# vd_using_sym.net
KiCad netlist of a schematic drawn in EAGLE
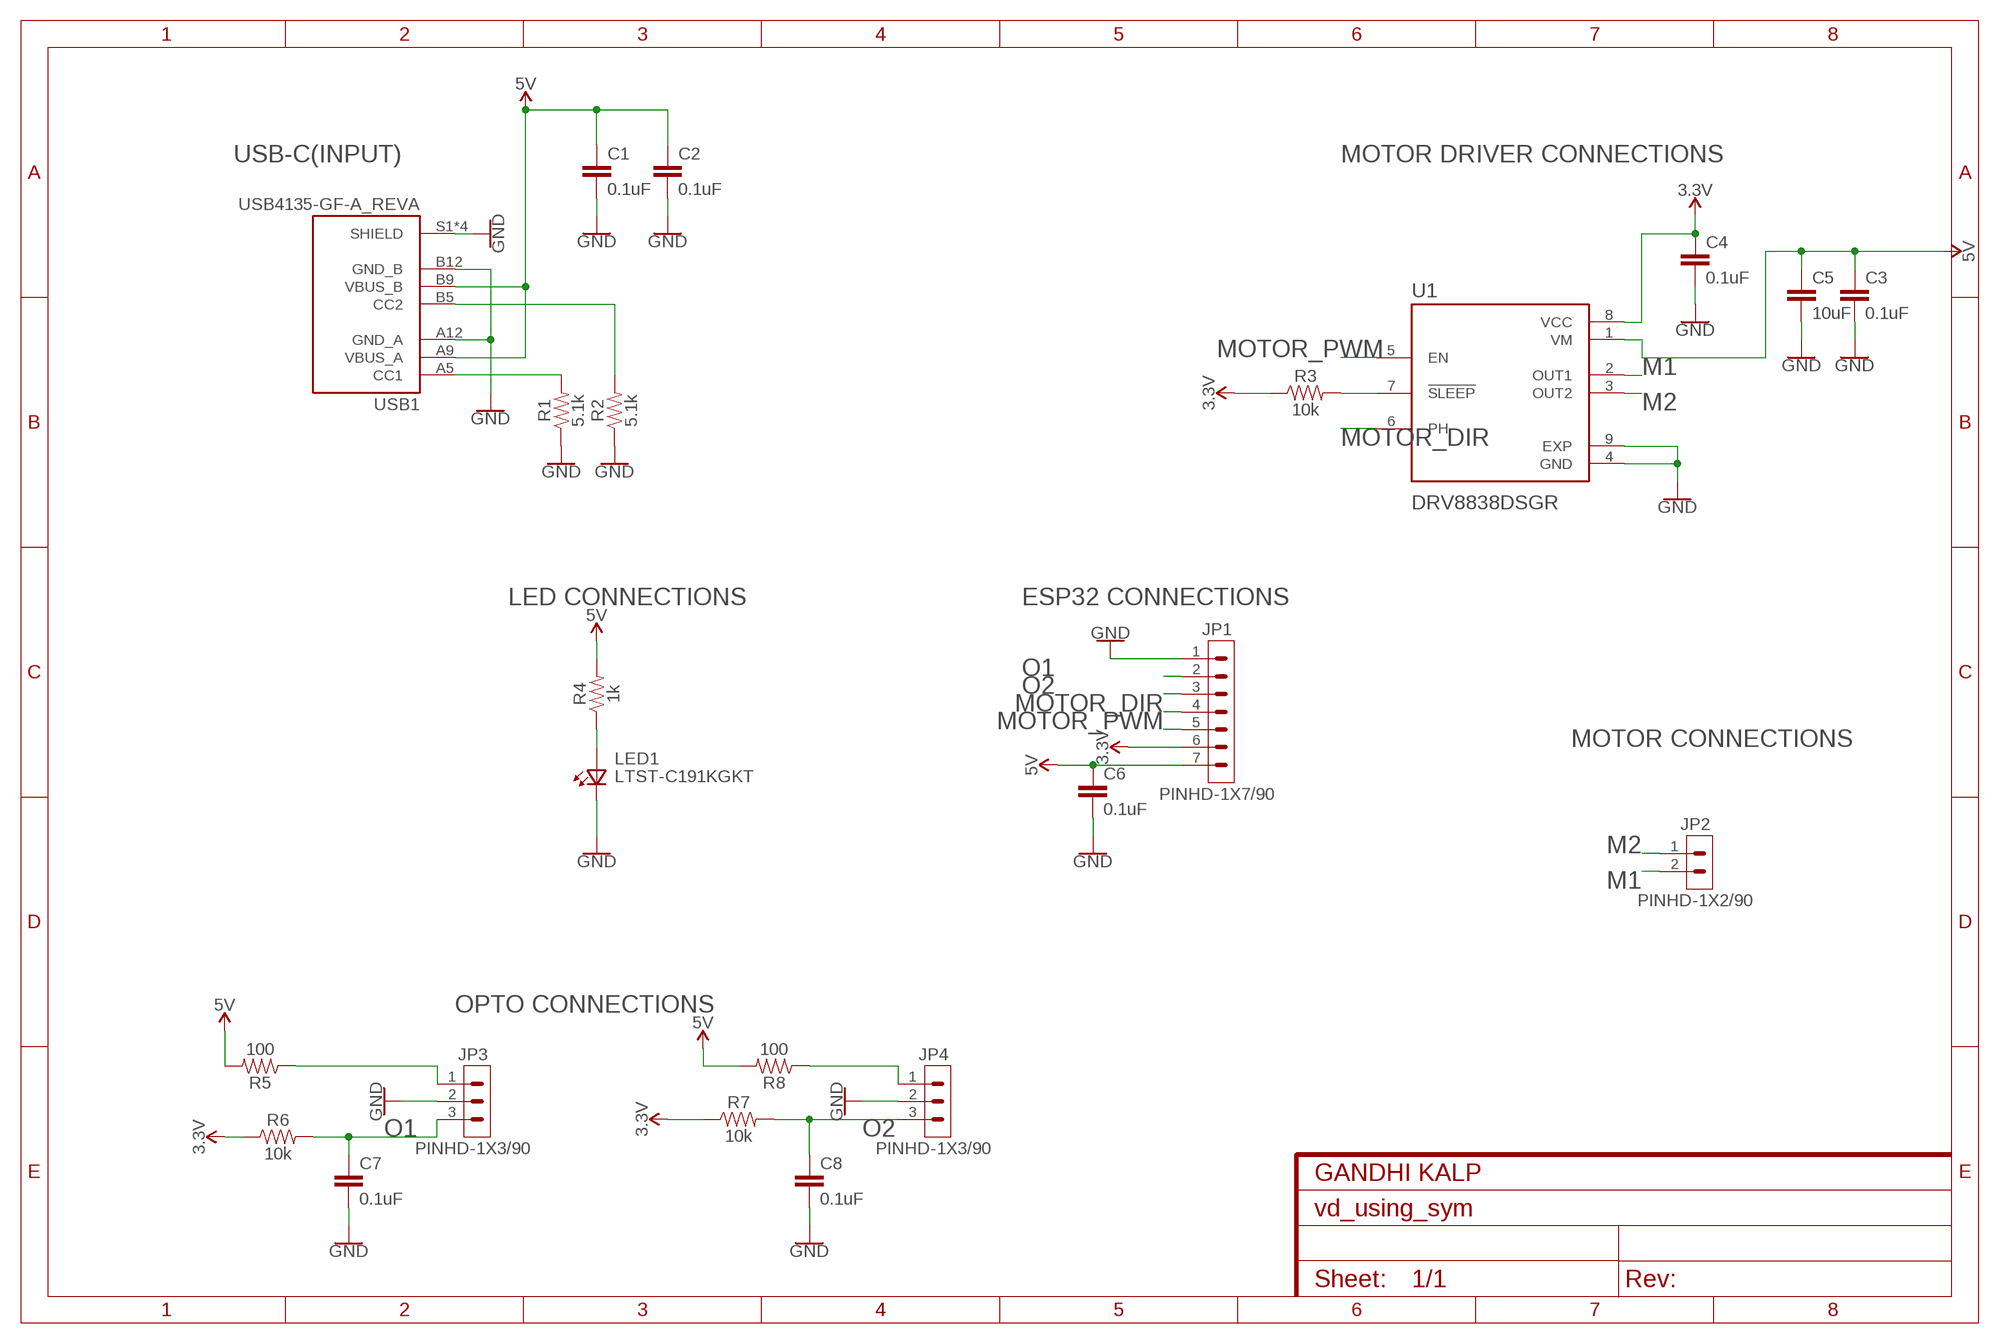
[diagram p0: schematic, sheet 1]

(export (version "E")
  (design (tool "Eeschema 10.0.6"))
  (components
    (comp (ref "C1")
      (value "0.1uF")
      (footprint "eagle-import:0402-TIGHT")
      (libsource (lib "eagle-import") (part "0.1UF-0402T-16V-10%-X7R-WE"))
    )
    (comp (ref "C2")
      (value "0.1uF")
      (footprint "eagle-import:0402-TIGHT")
      (libsource (lib "eagle-import") (part "0.1UF-0402T-16V-10%-X7R-WE"))
    )
    (comp (ref "C3")
      (value "0.1uF")
      (footprint "eagle-import:0402-TIGHT")
      (libsource (lib "eagle-import") (part "0.1UF-0402T-16V-10%-X7R-WE"))
    )
    (comp (ref "C4")
      (value "0.1uF")
      (footprint "eagle-import:0402-TIGHT")
      (libsource (lib "eagle-import") (part "0.1UF-0402T-16V-10%-X7R-WE"))
    )
    (comp (ref "C5")
      (value "10uF")
      (footprint "eagle-import:0805")
      (libsource (lib "eagle-import") (part "10UF-0805-25V-10%"))
    )
    (comp (ref "C6")
      (value "0.1uF")
      (footprint "eagle-import:0402-TIGHT")
      (libsource (lib "eagle-import") (part "0.1UF-0402T-16V-10%-X7R-WE"))
    )
    (comp (ref "C7")
      (value "0.1uF")
      (footprint "eagle-import:0402-TIGHT")
      (libsource (lib "eagle-import") (part "0.1UF-0402T-16V-10%-X7R-WE"))
    )
    (comp (ref "C8")
      (value "0.1uF")
      (footprint "eagle-import:0402-TIGHT")
      (libsource (lib "eagle-import") (part "0.1UF-0402T-16V-10%-X7R-WE"))
    )
    (comp (ref "JP1")
      (value "PINHD-1X7/90")
      (footprint "eagle-import:1X07_90")
      (libsource (lib "eagle-import") (part "PINHD-1X7/90"))
    )
    (comp (ref "JP2")
      (value "PINHD-1X2/90")
      (footprint "eagle-import:1X02_90")
      (libsource (lib "eagle-import") (part "PINHD-1X2/90"))
    )
    (comp (ref "JP3")
      (value "PINHD-1X3/90")
      (footprint "eagle-import:1X03_90")
      (libsource (lib "eagle-import") (part "PINHD-1X3/90"))
    )
    (comp (ref "JP4")
      (value "PINHD-1X3/90")
      (footprint "eagle-import:1X03_90")
      (libsource (lib "eagle-import") (part "PINHD-1X3/90"))
    )
    (comp (ref "LED1")
      (value "LTST-C191KGKT")
      (footprint "eagle-import:0603")
      (fields (field (name "MF") "Lite-On Electronics"))
      (libsource (lib "eagle-import") (part "LTST-C191KGKT"))
    )
    (comp (ref "R1")
      (value "5.1k")
      (footprint "eagle-import:0402-TIGHT")
      (libsource (lib "eagle-import") (part "5.1KOHM-0402T-1/16W-1%"))
    )
    (comp (ref "R2")
      (value "5.1k")
      (footprint "eagle-import:0402-TIGHT")
      (libsource (lib "eagle-import") (part "5.1KOHM-0402T-1/16W-1%"))
    )
    (comp (ref "R3")
      (value "10k")
      (footprint "eagle-import:0402-TIGHT")
      (libsource (lib "eagle-import") (part "10KOHM-0402T-1/16W-1%"))
    )
    (comp (ref "R4")
      (value "1k")
      (footprint "eagle-import:0402-TIGHT")
      (libsource (lib "eagle-import") (part "1KOHM-0402T-1/16W-1%"))
    )
    (comp (ref "R5")
      (value "100")
      (footprint "eagle-import:0402-TIGHT")
      (libsource (lib "eagle-import") (part "100OHM-0402-TIGHT-1/16W-1%"))
    )
    (comp (ref "R6")
      (value "10k")
      (footprint "eagle-import:0402-TIGHT")
      (libsource (lib "eagle-import") (part "10KOHM-0402T-1/16W-1%"))
    )
    (comp (ref "R7")
      (value "10k")
      (footprint "eagle-import:0402-TIGHT")
      (libsource (lib "eagle-import") (part "10KOHM-0402T-1/16W-1%"))
    )
    (comp (ref "R8")
      (value "100")
      (footprint "eagle-import:0402-TIGHT")
      (libsource (lib "eagle-import") (part "100OHM-0402-TIGHT-1/16W-1%"))
    )
    (comp (ref "U1")
      (value "DRV8838DSGR")
      (footprint "eagle-import:SON50P200X200X80-9N")
      (fields (field (name "MF") "Texas Instruments"))
      (libsource (lib "eagle-import") (part "DRV8838DSGR"))
    )
    (comp (ref "USB1")
      (value "USB4135-GF-A_REVA")
      (footprint "eagle-import:GCT_USB4135-GF-A_REVA")
      (fields (field (name "MF") "Global Connector Technology") (field (name "MP") "USB4135-GF-A"))
      (libsource (lib "eagle-import") (part "USB4135-GF-A_REVA"))
    )
  )
  (nets
    (net (code "1") (name "/M1") (class "Default")
      (node (ref "JP2") (pin "2") (pinfunction "2_2") (pintype "passive"))
      (node (ref "U1") (pin "2") (pinfunction "OUT1_2") (pintype "output"))
    )
    (net (code "2") (name "/M2") (class "Default")
      (node (ref "JP2") (pin "1") (pinfunction "1_1") (pintype "passive"))
      (node (ref "U1") (pin "3") (pinfunction "OUT2_3") (pintype "output"))
    )
    (net (code "3") (name "/MOTOR_DIR") (class "Default")
      (node (ref "JP1") (pin "4") (pinfunction "4_4") (pintype "passive"))
      (node (ref "U1") (pin "6") (pinfunction "PH_6") (pintype "input"))
    )
    (net (code "4") (name "/MOTOR_PWM") (class "Default")
      (node (ref "JP1") (pin "5") (pinfunction "5_5") (pintype "passive"))
      (node (ref "U1") (pin "5") (pinfunction "EN_5") (pintype "input"))
    )
    (net (code "5") (name "/O1") (class "Default")
      (node (ref "C7") (pin "1") (pinfunction "1_1") (pintype "passive"))
      (node (ref "JP1") (pin "2") (pinfunction "2_2") (pintype "passive"))
      (node (ref "JP3") (pin "3") (pinfunction "3_3") (pintype "passive"))
      (node (ref "R6") (pin "2") (pinfunction "2_2") (pintype "passive"))
    )
    (net (code "6") (name "/O2") (class "Default")
      (node (ref "C8") (pin "1") (pinfunction "1_1") (pintype "passive"))
      (node (ref "JP1") (pin "3") (pinfunction "3_3") (pintype "passive"))
      (node (ref "JP4") (pin "3") (pinfunction "3_3") (pintype "passive"))
      (node (ref "R7") (pin "2") (pinfunction "2_2") (pintype "passive"))
    )
    (net (code "7") (name "3.3V") (class "Default")
      (node (ref "C4") (pin "1") (pinfunction "1_1") (pintype "passive"))
      (node (ref "JP1") (pin "6") (pinfunction "6_6") (pintype "passive"))
      (node (ref "R3") (pin "1") (pinfunction "1_1") (pintype "passive"))
      (node (ref "R6") (pin "1") (pinfunction "1_1") (pintype "passive"))
      (node (ref "R7") (pin "1") (pinfunction "1_1") (pintype "passive"))
      (node (ref "U1") (pin "8") (pinfunction "VCC_8") (pintype "power_in"))
    )
    (net (code "8") (name "5V") (class "Default")
      (node (ref "C1") (pin "1") (pinfunction "1_1") (pintype "passive"))
      (node (ref "C2") (pin "1") (pinfunction "1_1") (pintype "passive"))
      (node (ref "C3") (pin "1") (pinfunction "1_1") (pintype "passive"))
      (node (ref "C5") (pin "1") (pinfunction "1_1") (pintype "passive"))
      (node (ref "C6") (pin "1") (pinfunction "1_1") (pintype "passive"))
      (node (ref "JP1") (pin "7") (pinfunction "7_7") (pintype "passive"))
      (node (ref "R4") (pin "2") (pinfunction "2_2") (pintype "passive"))
      (node (ref "R5") (pin "2") (pinfunction "2_2") (pintype "passive"))
      (node (ref "R8") (pin "2") (pinfunction "2_2") (pintype "passive"))
      (node (ref "U1") (pin "1") (pinfunction "VM_1") (pintype "power_in"))
      (node (ref "USB1") (pin "A9") (pinfunction "VBUS_A_A9") (pintype "power_in"))
      (node (ref "USB1") (pin "B9") (pinfunction "VBUS_B_B9") (pintype "power_in"))
    )
    (net (code "9") (name "GND") (class "Default")
      (node (ref "C1") (pin "2") (pinfunction "2_2") (pintype "passive"))
      (node (ref "C2") (pin "2") (pinfunction "2_2") (pintype "passive"))
      (node (ref "C3") (pin "2") (pinfunction "2_2") (pintype "passive"))
      (node (ref "C4") (pin "2") (pinfunction "2_2") (pintype "passive"))
      (node (ref "C5") (pin "2") (pinfunction "2_2") (pintype "passive"))
      (node (ref "C6") (pin "2") (pinfunction "2_2") (pintype "passive"))
      (node (ref "C7") (pin "2") (pinfunction "2_2") (pintype "passive"))
      (node (ref "C8") (pin "2") (pinfunction "2_2") (pintype "passive"))
      (node (ref "JP1") (pin "1") (pinfunction "1_1") (pintype "passive"))
      (node (ref "JP3") (pin "2") (pinfunction "2_2") (pintype "passive"))
      (node (ref "JP4") (pin "2") (pinfunction "2_2") (pintype "passive"))
      (node (ref "LED1") (pin "1") (pinfunction "K2_1") (pintype "passive"))
      (node (ref "R1") (pin "1") (pinfunction "1_1") (pintype "passive"))
      (node (ref "R2") (pin "1") (pinfunction "1_1") (pintype "passive"))
      (node (ref "U1") (pin "4") (pinfunction "GND_4") (pintype "power_in"))
      (node (ref "U1") (pin "9") (pinfunction "EXP_9") (pintype "power_in"))
      (node (ref "USB1") (pin "A12") (pinfunction "GND_A_A12") (pintype "power_in"))
      (node (ref "USB1") (pin "B12") (pinfunction "GND_B_B12") (pintype "power_in"))
      (node (ref "USB1") (pin "S1") (pinfunction "SHIELD_S1") (pintype "passive"))
      (node (ref "USB1") (pin "S2") (pinfunction "SHIELD_S2") (pintype "passive"))
      (node (ref "USB1") (pin "S3") (pinfunction "SHIELD_S3") (pintype "passive"))
      (node (ref "USB1") (pin "S4") (pinfunction "SHIELD_S4") (pintype "passive"))
    )
    (net (code "10") (name "Net-(JP3-Pad1)") (class "Default")
      (node (ref "JP3") (pin "1") (pinfunction "1_1") (pintype "passive"))
      (node (ref "R5") (pin "1") (pinfunction "1_1") (pintype "passive"))
    )
    (net (code "11") (name "Net-(JP4-Pad1)") (class "Default")
      (node (ref "JP4") (pin "1") (pinfunction "1_1") (pintype "passive"))
      (node (ref "R8") (pin "1") (pinfunction "1_1") (pintype "passive"))
    )
    (net (code "12") (name "Net-(LED1-A2)") (class "Default")
      (node (ref "LED1") (pin "2") (pinfunction "A2_2") (pintype "passive"))
      (node (ref "R4") (pin "1") (pinfunction "1_1") (pintype "passive"))
    )
    (net (code "13") (name "Net-(U1-~{SLEEP})") (class "Default")
      (node (ref "R3") (pin "2") (pinfunction "2_2") (pintype "passive"))
      (node (ref "U1") (pin "7") (pinfunction "~{SLEEP}_7") (pintype "input"))
    )
    (net (code "14") (name "Net-(USB1-CC1)") (class "Default")
      (node (ref "R1") (pin "2") (pinfunction "2_2") (pintype "passive"))
      (node (ref "USB1") (pin "A5") (pinfunction "CC1_A5") (pintype "bidirectional"))
    )
    (net (code "15") (name "Net-(USB1-CC2)") (class "Default")
      (node (ref "R2") (pin "2") (pinfunction "2_2") (pintype "passive"))
      (node (ref "USB1") (pin "B5") (pinfunction "CC2_B5") (pintype "bidirectional"))
    )
  )
)
